# 06_-_FUSES.net
KiCad netlist of a schematic drawn in Altium Designer
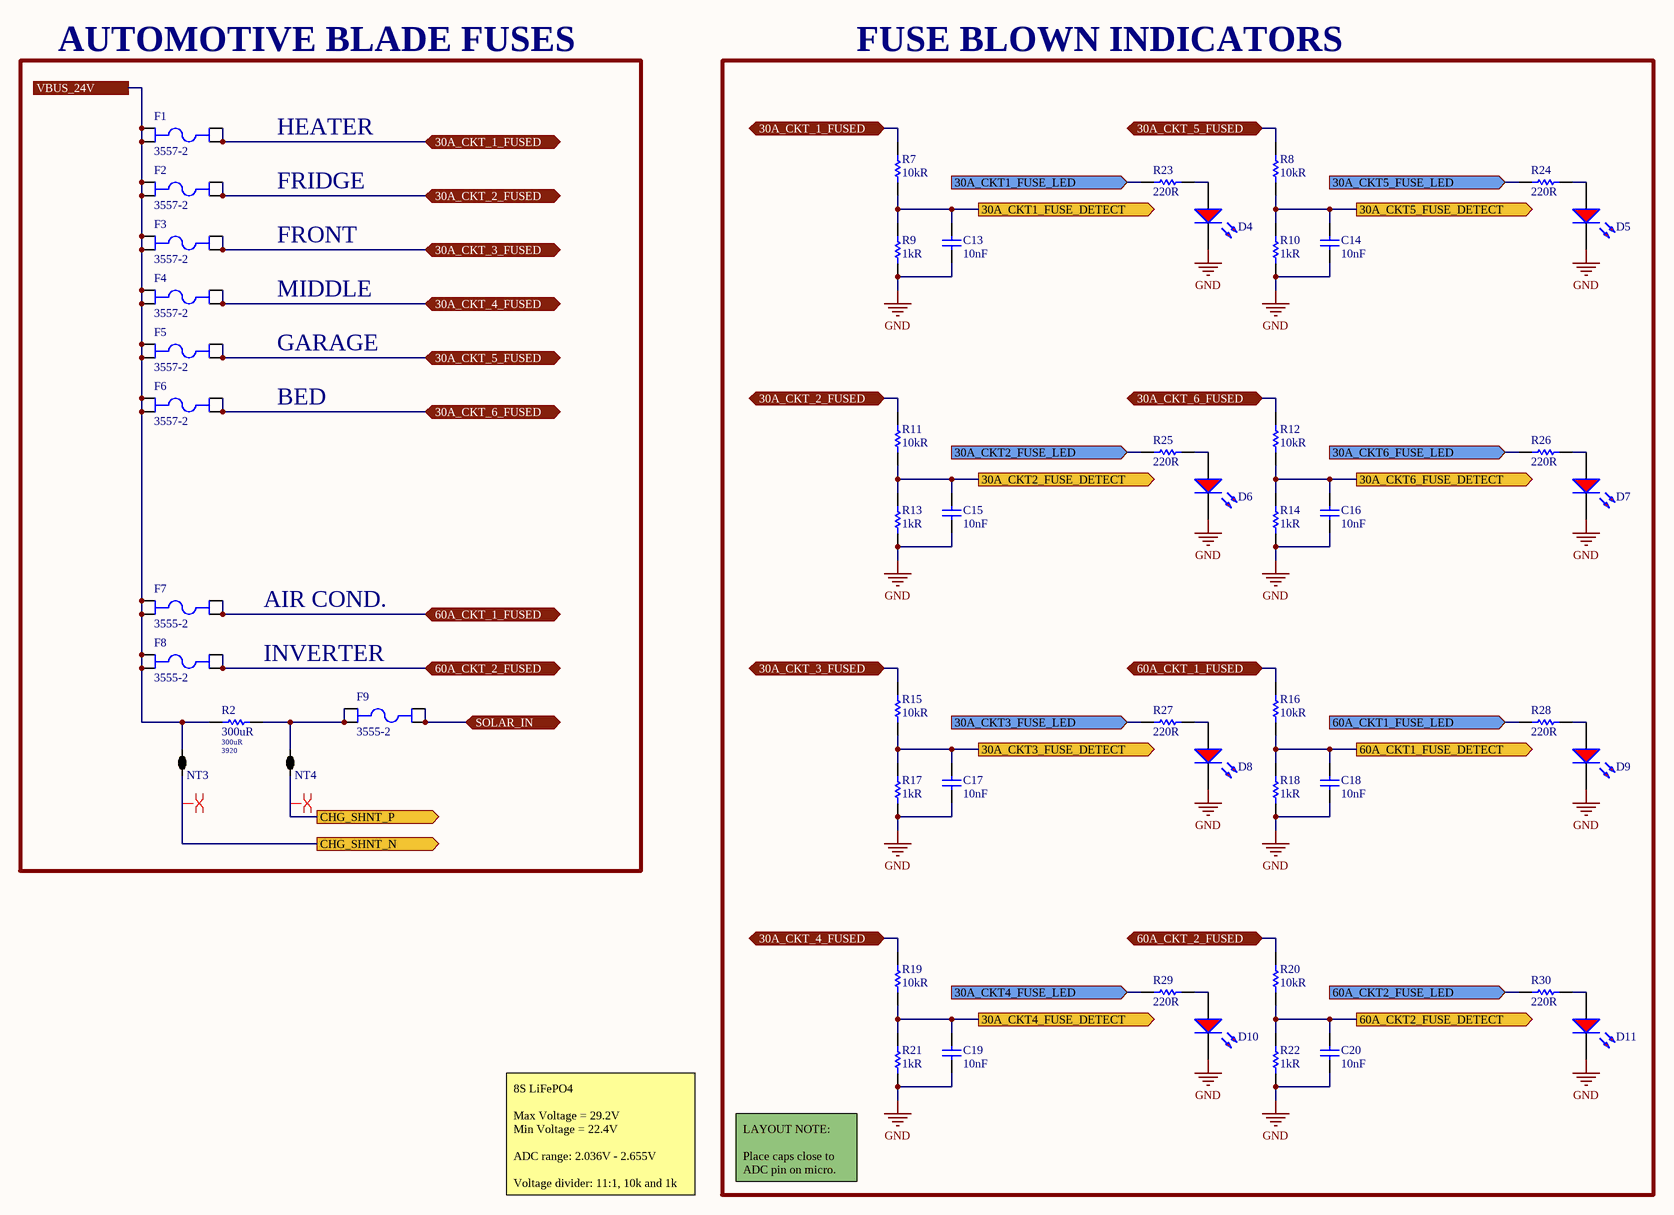
[diagram p0: [06] - FUSES.SchDoc]

(export (version "E")
  (design (tool "Eeschema 10.0.6"))
  (components
    (comp (ref "C13")
      (value "10nF")
      (footprint "INCH 0603 - METRIC 1608 - H087")
      (description "CAP CER 0603 10NF 16V X7R 10%")
      (fields
        (field (name "MANUFACTURER") "KEMET")
        (field (name "MANUFACTURER PART NUMBER") "C0603C103K4RECAUTO")
      )
      (libsource (lib "Capacitors") (part "C0603C103K4RECAUTO"))
    )
    (comp (ref "C14")
      (value "10nF")
      (footprint "INCH 0603 - METRIC 1608 - H087")
      (description "CAP CER 0603 10NF 16V X7R 10%")
      (fields
        (field (name "MANUFACTURER") "KEMET")
        (field (name "MANUFACTURER PART NUMBER") "C0603C103K4RECAUTO")
      )
      (libsource (lib "Capacitors") (part "C0603C103K4RECAUTO"))
    )
    (comp (ref "C15")
      (value "10nF")
      (footprint "INCH 0603 - METRIC 1608 - H087")
      (description "CAP CER 0603 10NF 16V X7R 10%")
      (fields
        (field (name "MANUFACTURER") "KEMET")
        (field (name "MANUFACTURER PART NUMBER") "C0603C103K4RECAUTO")
      )
      (libsource (lib "Capacitors") (part "C0603C103K4RECAUTO"))
    )
    (comp (ref "C16")
      (value "10nF")
      (footprint "INCH 0603 - METRIC 1608 - H087")
      (description "CAP CER 0603 10NF 16V X7R 10%")
      (fields
        (field (name "MANUFACTURER") "KEMET")
        (field (name "MANUFACTURER PART NUMBER") "C0603C103K4RECAUTO")
      )
      (libsource (lib "Capacitors") (part "C0603C103K4RECAUTO"))
    )
    (comp (ref "C17")
      (value "10nF")
      (footprint "INCH 0603 - METRIC 1608 - H087")
      (description "CAP CER 0603 10NF 16V X7R 10%")
      (fields
        (field (name "MANUFACTURER") "KEMET")
        (field (name "MANUFACTURER PART NUMBER") "C0603C103K4RECAUTO")
      )
      (libsource (lib "Capacitors") (part "C0603C103K4RECAUTO"))
    )
    (comp (ref "C18")
      (value "10nF")
      (footprint "INCH 0603 - METRIC 1608 - H087")
      (description "CAP CER 0603 10NF 16V X7R 10%")
      (fields
        (field (name "MANUFACTURER") "KEMET")
        (field (name "MANUFACTURER PART NUMBER") "C0603C103K4RECAUTO")
      )
      (libsource (lib "Capacitors") (part "C0603C103K4RECAUTO"))
    )
    (comp (ref "C19")
      (value "10nF")
      (footprint "INCH 0603 - METRIC 1608 - H087")
      (description "CAP CER 0603 10NF 16V X7R 10%")
      (fields
        (field (name "MANUFACTURER") "KEMET")
        (field (name "MANUFACTURER PART NUMBER") "C0603C103K4RECAUTO")
      )
      (libsource (lib "Capacitors") (part "C0603C103K4RECAUTO"))
    )
    (comp (ref "C20")
      (value "10nF")
      (footprint "INCH 0603 - METRIC 1608 - H087")
      (description "CAP CER 0603 10NF 16V X7R 10%")
      (fields
        (field (name "MANUFACTURER") "KEMET")
        (field (name "MANUFACTURER PART NUMBER") "C0603C103K4RECAUTO")
      )
      (libsource (lib "Capacitors") (part "C0603C103K4RECAUTO"))
    )
    (comp (ref "D4")
      (value "Red")
      (footprint "LED - 1206 - RED")
      (description "LED RED CLEAR 2SMD")
      (fields (field (name "MANUFACTURER PART NUMBER") "APT3216LSECK/J3-PRV"))
      (libsource (lib "LEDs") (part "APT3216LSECK/J3-PRV"))
    )
    (comp (ref "D5")
      (value "Red")
      (footprint "LED - 1206 - RED")
      (description "LED RED CLEAR 2SMD")
      (fields (field (name "MANUFACTURER PART NUMBER") "APT3216LSECK/J3-PRV"))
      (libsource (lib "LEDs") (part "APT3216LSECK/J3-PRV"))
    )
    (comp (ref "D6")
      (value "Red")
      (footprint "LED - 1206 - RED")
      (description "LED RED CLEAR 2SMD")
      (fields (field (name "MANUFACTURER PART NUMBER") "APT3216LSECK/J3-PRV"))
      (libsource (lib "LEDs") (part "APT3216LSECK/J3-PRV"))
    )
    (comp (ref "D7")
      (value "Red")
      (footprint "LED - 1206 - RED")
      (description "LED RED CLEAR 2SMD")
      (fields (field (name "MANUFACTURER PART NUMBER") "APT3216LSECK/J3-PRV"))
      (libsource (lib "LEDs") (part "APT3216LSECK/J3-PRV"))
    )
    (comp (ref "D8")
      (value "Red")
      (footprint "LED - 1206 - RED")
      (description "LED RED CLEAR 2SMD")
      (fields (field (name "MANUFACTURER PART NUMBER") "APT3216LSECK/J3-PRV"))
      (libsource (lib "LEDs") (part "APT3216LSECK/J3-PRV"))
    )
    (comp (ref "D9")
      (value "Red")
      (footprint "LED - 1206 - RED")
      (description "LED RED CLEAR 2SMD")
      (fields (field (name "MANUFACTURER PART NUMBER") "APT3216LSECK/J3-PRV"))
      (libsource (lib "LEDs") (part "APT3216LSECK/J3-PRV"))
    )
    (comp (ref "D10")
      (value "Red")
      (footprint "LED - 1206 - RED")
      (description "LED RED CLEAR 2SMD")
      (fields (field (name "MANUFACTURER PART NUMBER") "APT3216LSECK/J3-PRV"))
      (libsource (lib "LEDs") (part "APT3216LSECK/J3-PRV"))
    )
    (comp (ref "D11")
      (value "Red")
      (footprint "LED - 1206 - RED")
      (description "LED RED CLEAR 2SMD")
      (fields (field (name "MANUFACTURER PART NUMBER") "APT3216LSECK/J3-PRV"))
      (libsource (lib "LEDs") (part "APT3216LSECK/J3-PRV"))
    )
    (comp (ref "F1")
      (value "3557-2")
      (footprint "KEYSTONE_3557-2")
      (description "Fuse Holder; Auto; 2 in1 Blade; THM; 1 Fuse; Vertical; 30 Amps")
      (fields (field (name "MANUFACTURER") "Keystone Electronics") (field (name "VOLTAGE") "500V"))
      (libsource (lib "Fuses") (part "3557-2"))
    )
    (comp (ref "F2")
      (value "3557-2")
      (footprint "KEYSTONE_3557-2")
      (description "Fuse Holder; Auto; 2 in1 Blade; THM; 1 Fuse; Vertical; 30 Amps")
      (fields (field (name "MANUFACTURER") "Keystone Electronics") (field (name "VOLTAGE") "500V"))
      (libsource (lib "Fuses") (part "3557-2"))
    )
    (comp (ref "F3")
      (value "3557-2")
      (footprint "KEYSTONE_3557-2")
      (description "Fuse Holder; Auto; 2 in1 Blade; THM; 1 Fuse; Vertical; 30 Amps")
      (fields (field (name "MANUFACTURER") "Keystone Electronics") (field (name "VOLTAGE") "500V"))
      (libsource (lib "Fuses") (part "3557-2"))
    )
    (comp (ref "F4")
      (value "3557-2")
      (footprint "KEYSTONE_3557-2")
      (description "Fuse Holder; Auto; 2 in1 Blade; THM; 1 Fuse; Vertical; 30 Amps")
      (fields (field (name "MANUFACTURER") "Keystone Electronics") (field (name "VOLTAGE") "500V"))
      (libsource (lib "Fuses") (part "3557-2"))
    )
    (comp (ref "F5")
      (value "3557-2")
      (footprint "KEYSTONE_3557-2")
      (description "Fuse Holder; Auto; 2 in1 Blade; THM; 1 Fuse; Vertical; 30 Amps")
      (fields (field (name "MANUFACTURER") "Keystone Electronics") (field (name "VOLTAGE") "500V"))
      (libsource (lib "Fuses") (part "3557-2"))
    )
    (comp (ref "F6")
      (value "3557-2")
      (footprint "KEYSTONE_3557-2")
      (description "Fuse Holder; Auto; 2 in1 Blade; THM; 1 Fuse; Vertical; 30 Amps")
      (fields (field (name "MANUFACTURER") "Keystone Electronics") (field (name "VOLTAGE") "500V"))
      (libsource (lib "Fuses") (part "3557-2"))
    )
    (comp (ref "F7")
      (value "3555-2")
      (footprint "KEYSTONE_3555-2")
      (description "Fuse Block Cartridge Holder")
      (fields (field (name "MANUFACTURER") "Keystone Electronics") (field (name "VOLTAGE") "500V"))
      (libsource (lib "Fuses") (part "3555-2"))
    )
    (comp (ref "F8")
      (value "3555-2")
      (footprint "KEYSTONE_3555-2")
      (description "Fuse Block Cartridge Holder")
      (fields (field (name "MANUFACTURER") "Keystone Electronics") (field (name "VOLTAGE") "500V"))
      (libsource (lib "Fuses") (part "3555-2"))
    )
    (comp (ref "F9")
      (value "3555-2")
      (footprint "KEYSTONE_3555-2")
      (description "Fuse Block Cartridge Holder")
      (fields (field (name "MANUFACTURER") "Keystone Electronics") (field (name "VOLTAGE") "500V"))
      (libsource (lib "Fuses") (part "3555-2"))
    )
    (comp (ref "NT3")
      (value "2 way net tie junction")
      (footprint "2way_LP")
      (libsource (lib "Net Ties") (part "2way"))
    )
    (comp (ref "NT4")
      (value "2 way net tie junction")
      (footprint "2way_LP")
      (libsource (lib "Net Ties") (part "2way"))
    )
    (comp (ref "R2")
      (value "300uR")
      (footprint "VISHAY_3920")
      (description "CSM3920A 0R0030 1.0% S T 130800 Chip Resistor Strip 3920 (1052 Metric)")
      (fields
        (field (name "MANUFACTURER") "Vishay Precision Group")
        (field (name "MANUFACTURER PART NUMBER") "Y14840R00030F9R")
        (field (name "RESISTANCE") "300uR")
        (field (name "PACKAGE") "3920")
      )
      (libsource (lib "Resistors") (part "Y14840R00030F9R"))
    )
    (comp (ref "R7")
      (value "10kR")
      (footprint "INCH 0603 - METRIC 1508 - H050")
      (description "RES SMD 10K OHM 0.5% 1/16W 0603")
      (fields
        (field (name "MANUFACTURER") "Susumu")
        (field (name "MANUFACTURER PART NUMBER") "RR0816P-103-D")
      )
      (libsource (lib "Resistors") (part "RR0816P-103-D"))
    )
    (comp (ref "R8")
      (value "10kR")
      (footprint "INCH 0603 - METRIC 1508 - H050")
      (description "RES SMD 10K OHM 0.5% 1/16W 0603")
      (fields
        (field (name "MANUFACTURER") "Susumu")
        (field (name "MANUFACTURER PART NUMBER") "RR0816P-103-D")
      )
      (libsource (lib "Resistors") (part "RR0816P-103-D"))
    )
    (comp (ref "R9")
      (value "1kR")
      (footprint "INCH 0603 - METRIC 1508 - H050")
      (description "RES SMD 1K OHM 1% 1/10W 0603")
      (fields
        (field (name "MANUFACTURER") "Vishay Dale")
        (field (name "MANUFACTURER PART NUMBER") "CRCW06031K00FKEA")
      )
      (libsource (lib "Resistors") (part "CRCW06031K00FKEA"))
    )
    (comp (ref "R10")
      (value "1kR")
      (footprint "INCH 0603 - METRIC 1508 - H050")
      (description "RES SMD 1K OHM 1% 1/10W 0603")
      (fields
        (field (name "MANUFACTURER") "Vishay Dale")
        (field (name "MANUFACTURER PART NUMBER") "CRCW06031K00FKEA")
      )
      (libsource (lib "Resistors") (part "CRCW06031K00FKEA"))
    )
    (comp (ref "R11")
      (value "10kR")
      (footprint "INCH 0603 - METRIC 1508 - H050")
      (description "RES SMD 10K OHM 0.5% 1/16W 0603")
      (fields
        (field (name "MANUFACTURER") "Susumu")
        (field (name "MANUFACTURER PART NUMBER") "RR0816P-103-D")
      )
      (libsource (lib "Resistors") (part "RR0816P-103-D"))
    )
    (comp (ref "R12")
      (value "10kR")
      (footprint "INCH 0603 - METRIC 1508 - H050")
      (description "RES SMD 10K OHM 0.5% 1/16W 0603")
      (fields
        (field (name "MANUFACTURER") "Susumu")
        (field (name "MANUFACTURER PART NUMBER") "RR0816P-103-D")
      )
      (libsource (lib "Resistors") (part "RR0816P-103-D"))
    )
    (comp (ref "R13")
      (value "1kR")
      (footprint "INCH 0603 - METRIC 1508 - H050")
      (description "RES SMD 1K OHM 1% 1/10W 0603")
      (fields
        (field (name "MANUFACTURER") "Vishay Dale")
        (field (name "MANUFACTURER PART NUMBER") "CRCW06031K00FKEA")
      )
      (libsource (lib "Resistors") (part "CRCW06031K00FKEA"))
    )
    (comp (ref "R14")
      (value "1kR")
      (footprint "INCH 0603 - METRIC 1508 - H050")
      (description "RES SMD 1K OHM 1% 1/10W 0603")
      (fields
        (field (name "MANUFACTURER") "Vishay Dale")
        (field (name "MANUFACTURER PART NUMBER") "CRCW06031K00FKEA")
      )
      (libsource (lib "Resistors") (part "CRCW06031K00FKEA"))
    )
    (comp (ref "R15")
      (value "10kR")
      (footprint "INCH 0603 - METRIC 1508 - H050")
      (description "RES SMD 10K OHM 0.5% 1/16W 0603")
      (fields
        (field (name "MANUFACTURER") "Susumu")
        (field (name "MANUFACTURER PART NUMBER") "RR0816P-103-D")
      )
      (libsource (lib "Resistors") (part "RR0816P-103-D"))
    )
    (comp (ref "R16")
      (value "10kR")
      (footprint "INCH 0603 - METRIC 1508 - H050")
      (description "RES SMD 10K OHM 0.5% 1/16W 0603")
      (fields
        (field (name "MANUFACTURER") "Susumu")
        (field (name "MANUFACTURER PART NUMBER") "RR0816P-103-D")
      )
      (libsource (lib "Resistors") (part "RR0816P-103-D"))
    )
    (comp (ref "R17")
      (value "1kR")
      (footprint "INCH 0603 - METRIC 1508 - H050")
      (description "RES SMD 1K OHM 1% 1/10W 0603")
      (fields
        (field (name "MANUFACTURER") "Vishay Dale")
        (field (name "MANUFACTURER PART NUMBER") "CRCW06031K00FKEA")
      )
      (libsource (lib "Resistors") (part "CRCW06031K00FKEA"))
    )
    (comp (ref "R18")
      (value "1kR")
      (footprint "INCH 0603 - METRIC 1508 - H050")
      (description "RES SMD 1K OHM 1% 1/10W 0603")
      (fields
        (field (name "MANUFACTURER") "Vishay Dale")
        (field (name "MANUFACTURER PART NUMBER") "CRCW06031K00FKEA")
      )
      (libsource (lib "Resistors") (part "CRCW06031K00FKEA"))
    )
    (comp (ref "R19")
      (value "10kR")
      (footprint "INCH 0603 - METRIC 1508 - H050")
      (description "RES SMD 10K OHM 0.5% 1/16W 0603")
      (fields
        (field (name "MANUFACTURER") "Susumu")
        (field (name "MANUFACTURER PART NUMBER") "RR0816P-103-D")
      )
      (libsource (lib "Resistors") (part "RR0816P-103-D"))
    )
    (comp (ref "R20")
      (value "10kR")
      (footprint "INCH 0603 - METRIC 1508 - H050")
      (description "RES SMD 10K OHM 0.5% 1/16W 0603")
      (fields
        (field (name "MANUFACTURER") "Susumu")
        (field (name "MANUFACTURER PART NUMBER") "RR0816P-103-D")
      )
      (libsource (lib "Resistors") (part "RR0816P-103-D"))
    )
    (comp (ref "R21")
      (value "1kR")
      (footprint "INCH 0603 - METRIC 1508 - H050")
      (description "RES SMD 1K OHM 1% 1/10W 0603")
      (fields
        (field (name "MANUFACTURER") "Vishay Dale")
        (field (name "MANUFACTURER PART NUMBER") "CRCW06031K00FKEA")
      )
      (libsource (lib "Resistors") (part "CRCW06031K00FKEA"))
    )
    (comp (ref "R22")
      (value "1kR")
      (footprint "INCH 0603 - METRIC 1508 - H050")
      (description "RES SMD 1K OHM 1% 1/10W 0603")
      (fields
        (field (name "MANUFACTURER") "Vishay Dale")
        (field (name "MANUFACTURER PART NUMBER") "CRCW06031K00FKEA")
      )
      (libsource (lib "Resistors") (part "CRCW06031K00FKEA"))
    )
    (comp (ref "R23")
      (value "220R")
      (footprint "INCH 0603 - METRIC 1608 - H055")
      (description "RES SMD 220 OHM 1% 1/10W 0603")
      (fields
        (field (name "MANUFACTURER") "Yageo")
        (field (name "MANUFACTURER PART NUMBER") "RC0603FR-07220RL")
      )
      (libsource (lib "Resistors") (part "RC0603FR-07220RL"))
    )
    (comp (ref "R24")
      (value "220R")
      (footprint "INCH 0603 - METRIC 1608 - H055")
      (description "RES SMD 220 OHM 1% 1/10W 0603")
      (fields
        (field (name "MANUFACTURER") "Yageo")
        (field (name "MANUFACTURER PART NUMBER") "RC0603FR-07220RL")
      )
      (libsource (lib "Resistors") (part "RC0603FR-07220RL"))
    )
    (comp (ref "R25")
      (value "220R")
      (footprint "INCH 0603 - METRIC 1608 - H055")
      (description "RES SMD 220 OHM 1% 1/10W 0603")
      (fields
        (field (name "MANUFACTURER") "Yageo")
        (field (name "MANUFACTURER PART NUMBER") "RC0603FR-07220RL")
      )
      (libsource (lib "Resistors") (part "RC0603FR-07220RL"))
    )
    (comp (ref "R26")
      (value "220R")
      (footprint "INCH 0603 - METRIC 1608 - H055")
      (description "RES SMD 220 OHM 1% 1/10W 0603")
      (fields
        (field (name "MANUFACTURER") "Yageo")
        (field (name "MANUFACTURER PART NUMBER") "RC0603FR-07220RL")
      )
      (libsource (lib "Resistors") (part "RC0603FR-07220RL"))
    )
    (comp (ref "R27")
      (value "220R")
      (footprint "INCH 0603 - METRIC 1608 - H055")
      (description "RES SMD 220 OHM 1% 1/10W 0603")
      (fields
        (field (name "MANUFACTURER") "Yageo")
        (field (name "MANUFACTURER PART NUMBER") "RC0603FR-07220RL")
      )
      (libsource (lib "Resistors") (part "RC0603FR-07220RL"))
    )
    (comp (ref "R28")
      (value "220R")
      (footprint "INCH 0603 - METRIC 1608 - H055")
      (description "RES SMD 220 OHM 1% 1/10W 0603")
      (fields
        (field (name "MANUFACTURER") "Yageo")
        (field (name "MANUFACTURER PART NUMBER") "RC0603FR-07220RL")
      )
      (libsource (lib "Resistors") (part "RC0603FR-07220RL"))
    )
    (comp (ref "R29")
      (value "220R")
      (footprint "INCH 0603 - METRIC 1608 - H055")
      (description "RES SMD 220 OHM 1% 1/10W 0603")
      (fields
        (field (name "MANUFACTURER") "Yageo")
        (field (name "MANUFACTURER PART NUMBER") "RC0603FR-07220RL")
      )
      (libsource (lib "Resistors") (part "RC0603FR-07220RL"))
    )
    (comp (ref "R30")
      (value "220R")
      (footprint "INCH 0603 - METRIC 1608 - H055")
      (description "RES SMD 220 OHM 1% 1/10W 0603")
      (fields
        (field (name "MANUFACTURER") "Yageo")
        (field (name "MANUFACTURER PART NUMBER") "RC0603FR-07220RL")
      )
      (libsource (lib "Resistors") (part "RC0603FR-07220RL"))
    )
  )
  (nets
    (net (code "1") (name "/30A_CKT1_FUSE_DETECT") (class "Default")
      (node (ref "C13") (pin "2") (pintype "passive"))
      (node (ref "R7") (pin "1") (pintype "passive"))
      (node (ref "R9") (pin "2") (pintype "passive"))
    )
    (net (code "2") (name "/30A_CKT1_FUSE_LED") (class "Default")
      (node (ref "R23") (pin "1") (pintype "passive"))
    )
    (net (code "3") (name "/30A_CKT2_FUSE_DETECT") (class "Default")
      (node (ref "C15") (pin "2") (pintype "passive"))
      (node (ref "R11") (pin "1") (pintype "passive"))
      (node (ref "R13") (pin "2") (pintype "passive"))
    )
    (net (code "4") (name "/30A_CKT2_FUSE_LED") (class "Default")
      (node (ref "R25") (pin "1") (pintype "passive"))
    )
    (net (code "5") (name "/30A_CKT3_FUSE_DETECT") (class "Default")
      (node (ref "C17") (pin "2") (pintype "passive"))
      (node (ref "R15") (pin "1") (pintype "passive"))
      (node (ref "R17") (pin "2") (pintype "passive"))
    )
    (net (code "6") (name "/30A_CKT3_FUSE_LED") (class "Default")
      (node (ref "R27") (pin "1") (pintype "passive"))
    )
    (net (code "7") (name "/30A_CKT4_FUSE_DETECT") (class "Default")
      (node (ref "C19") (pin "2") (pintype "passive"))
      (node (ref "R19") (pin "1") (pintype "passive"))
      (node (ref "R21") (pin "2") (pintype "passive"))
    )
    (net (code "8") (name "/30A_CKT4_FUSE_LED") (class "Default")
      (node (ref "R29") (pin "1") (pintype "passive"))
    )
    (net (code "9") (name "/30A_CKT5_FUSE_DETECT") (class "Default")
      (node (ref "C14") (pin "2") (pintype "passive"))
      (node (ref "R10") (pin "2") (pintype "passive"))
      (node (ref "R8") (pin "1") (pintype "passive"))
    )
    (net (code "10") (name "/30A_CKT5_FUSE_LED") (class "Default")
      (node (ref "R24") (pin "1") (pintype "passive"))
    )
    (net (code "11") (name "/30A_CKT6_FUSE_DETECT") (class "Default")
      (node (ref "C16") (pin "2") (pintype "passive"))
      (node (ref "R12") (pin "1") (pintype "passive"))
      (node (ref "R14") (pin "2") (pintype "passive"))
    )
    (net (code "12") (name "/30A_CKT6_FUSE_LED") (class "Default")
      (node (ref "R26") (pin "1") (pintype "passive"))
    )
    (net (code "13") (name "/30A_CKT_1_FUSED") (class "Default")
      (node (ref "F1") (pin "3") (pinfunction "3_3") (pintype "passive"))
      (node (ref "F1") (pin "4") (pinfunction "4_4") (pintype "passive"))
      (node (ref "R7") (pin "2") (pintype "passive"))
    )
    (net (code "14") (name "/30A_CKT_2_FUSED") (class "Default")
      (node (ref "F2") (pin "3") (pinfunction "3_3") (pintype "passive"))
      (node (ref "F2") (pin "4") (pinfunction "4_4") (pintype "passive"))
      (node (ref "R11") (pin "2") (pintype "passive"))
    )
    (net (code "15") (name "/30A_CKT_3_FUSED") (class "Default")
      (node (ref "F3") (pin "3") (pinfunction "3_3") (pintype "passive"))
      (node (ref "F3") (pin "4") (pinfunction "4_4") (pintype "passive"))
      (node (ref "R15") (pin "2") (pintype "passive"))
    )
    (net (code "16") (name "/30A_CKT_4_FUSED") (class "Default")
      (node (ref "F4") (pin "3") (pinfunction "3_3") (pintype "passive"))
      (node (ref "F4") (pin "4") (pinfunction "4_4") (pintype "passive"))
      (node (ref "R19") (pin "2") (pintype "passive"))
    )
    (net (code "17") (name "/30A_CKT_5_FUSED") (class "Default")
      (node (ref "F5") (pin "3") (pinfunction "3_3") (pintype "passive"))
      (node (ref "F5") (pin "4") (pinfunction "4_4") (pintype "passive"))
      (node (ref "R8") (pin "2") (pintype "passive"))
    )
    (net (code "18") (name "/30A_CKT_6_FUSED") (class "Default")
      (node (ref "F6") (pin "3") (pinfunction "3_3") (pintype "passive"))
      (node (ref "F6") (pin "4") (pinfunction "4_4") (pintype "passive"))
      (node (ref "R12") (pin "2") (pintype "passive"))
    )
    (net (code "19") (name "/60A_CKT1_FUSE_DETECT") (class "Default")
      (node (ref "C18") (pin "2") (pintype "passive"))
      (node (ref "R16") (pin "1") (pintype "passive"))
      (node (ref "R18") (pin "2") (pintype "passive"))
    )
    (net (code "20") (name "/60A_CKT1_FUSE_LED") (class "Default")
      (node (ref "R28") (pin "1") (pintype "passive"))
    )
    (net (code "21") (name "/60A_CKT2_FUSE_DETECT") (class "Default")
      (node (ref "C20") (pin "2") (pintype "passive"))
      (node (ref "R20") (pin "1") (pintype "passive"))
      (node (ref "R22") (pin "2") (pintype "passive"))
    )
    (net (code "22") (name "/60A_CKT2_FUSE_LED") (class "Default")
      (node (ref "R30") (pin "1") (pintype "passive"))
    )
    (net (code "23") (name "/60A_CKT_1_FUSED") (class "Default")
      (node (ref "F7") (pin "3") (pinfunction "3_3") (pintype "passive"))
      (node (ref "F7") (pin "4") (pinfunction "4_4") (pintype "passive"))
      (node (ref "R16") (pin "2") (pintype "passive"))
    )
    (net (code "24") (name "/60A_CKT_2_FUSED") (class "Default")
      (node (ref "F8") (pin "3") (pinfunction "3_3") (pintype "passive"))
      (node (ref "F8") (pin "4") (pinfunction "4_4") (pintype "passive"))
      (node (ref "R20") (pin "2") (pintype "passive"))
    )
    (net (code "25") (name "/CHG_SHNT_N") (class "Default")
      (node (ref "NT3") (pin "1") (pinfunction "1_1") (pintype "passive"))
    )
    (net (code "26") (name "/CHG_SHNT_P") (class "Default")
      (node (ref "NT4") (pin "1") (pinfunction "1_1") (pintype "passive"))
    )
    (net (code "27") (name "/SOLAR_IN") (class "Default")
      (node (ref "F9") (pin "3") (pinfunction "3_3") (pintype "passive"))
      (node (ref "F9") (pin "4") (pinfunction "4_4") (pintype "passive"))
    )
    (net (code "28") (name "/VBUS_24V") (class "Default")
      (node (ref "F1") (pin "1") (pinfunction "1_1") (pintype "passive"))
      (node (ref "F1") (pin "2") (pinfunction "2_2") (pintype "passive"))
      (node (ref "F2") (pin "1") (pinfunction "1_1") (pintype "passive"))
      (node (ref "F2") (pin "2") (pinfunction "2_2") (pintype "passive"))
      (node (ref "F3") (pin "1") (pinfunction "1_1") (pintype "passive"))
      (node (ref "F3") (pin "2") (pinfunction "2_2") (pintype "passive"))
      (node (ref "F4") (pin "1") (pinfunction "1_1") (pintype "passive"))
      (node (ref "F4") (pin "2") (pinfunction "2_2") (pintype "passive"))
      (node (ref "F5") (pin "1") (pinfunction "1_1") (pintype "passive"))
      (node (ref "F5") (pin "2") (pinfunction "2_2") (pintype "passive"))
      (node (ref "F6") (pin "1") (pinfunction "1_1") (pintype "passive"))
      (node (ref "F6") (pin "2") (pinfunction "2_2") (pintype "passive"))
      (node (ref "F7") (pin "1") (pinfunction "1_1") (pintype "passive"))
      (node (ref "F7") (pin "2") (pinfunction "2_2") (pintype "passive"))
      (node (ref "F8") (pin "1") (pinfunction "1_1") (pintype "passive"))
      (node (ref "F8") (pin "2") (pinfunction "2_2") (pintype "passive"))
      (node (ref "NT3") (pin "2") (pinfunction "2_2") (pintype "passive"))
      (node (ref "R2") (pin "1") (pintype "passive"))
    )
    (net (code "29") (name "GND") (class "Default")
      (node (ref "C13") (pin "1") (pintype "passive"))
      (node (ref "C14") (pin "1") (pintype "passive"))
      (node (ref "C15") (pin "1") (pintype "passive"))
      (node (ref "C16") (pin "1") (pintype "passive"))
      (node (ref "C17") (pin "1") (pintype "passive"))
      (node (ref "C18") (pin "1") (pintype "passive"))
      (node (ref "C19") (pin "1") (pintype "passive"))
      (node (ref "C20") (pin "1") (pintype "passive"))
      (node (ref "D10") (pin "C") (pintype "passive"))
      (node (ref "D11") (pin "C") (pintype "passive"))
      (node (ref "D4") (pin "C") (pintype "passive"))
      (node (ref "D5") (pin "C") (pintype "passive"))
      (node (ref "D6") (pin "C") (pintype "passive"))
      (node (ref "D7") (pin "C") (pintype "passive"))
      (node (ref "D8") (pin "C") (pintype "passive"))
      (node (ref "D9") (pin "C") (pintype "passive"))
      (node (ref "R10") (pin "1") (pintype "passive"))
      (node (ref "R13") (pin "1") (pintype "passive"))
      (node (ref "R14") (pin "1") (pintype "passive"))
      (node (ref "R17") (pin "1") (pintype "passive"))
      (node (ref "R18") (pin "1") (pintype "passive"))
      (node (ref "R21") (pin "1") (pintype "passive"))
      (node (ref "R22") (pin "1") (pintype "passive"))
      (node (ref "R9") (pin "1") (pintype "passive"))
    )
    (net (code "30") (name "Net-(D4-PadA)") (class "Default")
      (node (ref "D4") (pin "A") (pintype "passive"))
      (node (ref "R23") (pin "2") (pintype "passive"))
    )
    (net (code "31") (name "Net-(D5-PadA)") (class "Default")
      (node (ref "D5") (pin "A") (pintype "passive"))
      (node (ref "R24") (pin "2") (pintype "passive"))
    )
    (net (code "32") (name "Net-(D6-PadA)") (class "Default")
      (node (ref "D6") (pin "A") (pintype "passive"))
      (node (ref "R25") (pin "2") (pintype "passive"))
    )
    (net (code "33") (name "Net-(D7-PadA)") (class "Default")
      (node (ref "D7") (pin "A") (pintype "passive"))
      (node (ref "R26") (pin "2") (pintype "passive"))
    )
    (net (code "34") (name "Net-(D8-PadA)") (class "Default")
      (node (ref "D8") (pin "A") (pintype "passive"))
      (node (ref "R27") (pin "2") (pintype "passive"))
    )
    (net (code "35") (name "Net-(D9-PadA)") (class "Default")
      (node (ref "D9") (pin "A") (pintype "passive"))
      (node (ref "R28") (pin "2") (pintype "passive"))
    )
    (net (code "36") (name "Net-(D10-PadA)") (class "Default")
      (node (ref "D10") (pin "A") (pintype "passive"))
      (node (ref "R29") (pin "2") (pintype "passive"))
    )
    (net (code "37") (name "Net-(D11-PadA)") (class "Default")
      (node (ref "D11") (pin "A") (pintype "passive"))
      (node (ref "R30") (pin "2") (pintype "passive"))
    )
    (net (code "38") (name "Net-(F9-Pad1)") (class "Default")
      (node (ref "F9") (pin "1") (pinfunction "1_1") (pintype "passive"))
      (node (ref "F9") (pin "2") (pinfunction "2_2") (pintype "passive"))
      (node (ref "NT4") (pin "2") (pinfunction "2_2") (pintype "passive"))
      (node (ref "R2") (pin "2") (pintype "passive"))
    )
  )
)
